# RT1064_CoreBoard.net
KiCad netlist of a schematic drawn in Altium Designer
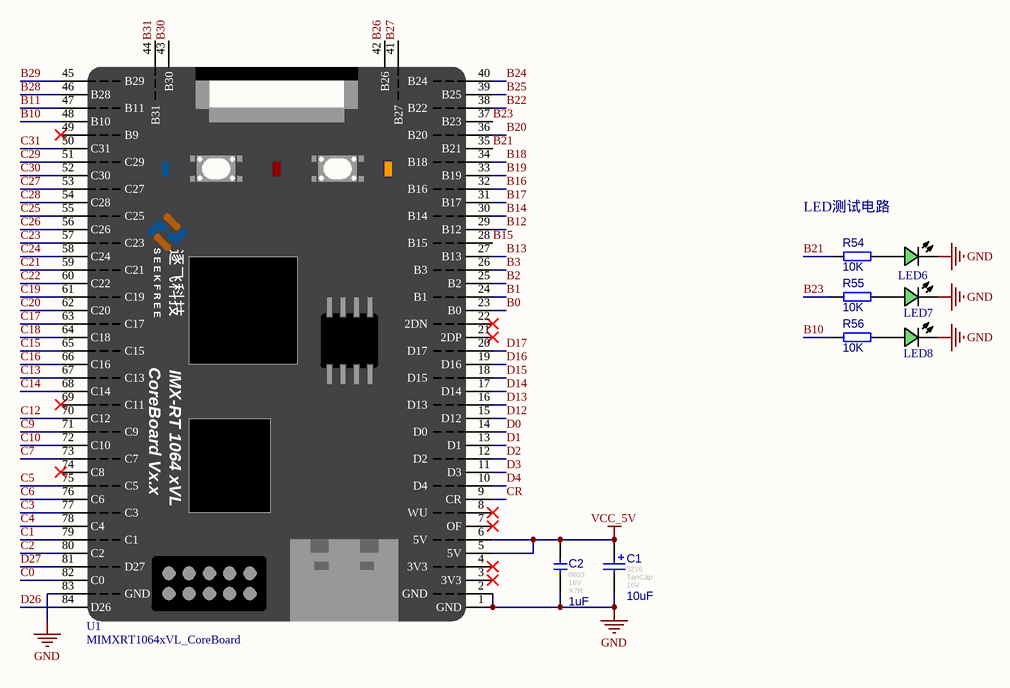
[diagram p0: RT1064_CoreBoard.SchDoc]

(export (version "E")
  (design (tool "Eeschema 10.0.6"))
  (components
    (comp (ref "C1")
      (value "10uF")
      (footprint "3216")
      (description "贴片钽电容 10uF 3216 16V")
      (fields
        (field (name "TYPE") "TanCap")
        (field (name "VOLTAGE") "16V")
        (field (name "Comment") "T-S 10uF 3216 16V")
      )
      (libsource (lib "RT1064_V1主板器件封装集成库") (part "T-S 10uF 3216 16V"))
    )
    (comp (ref "C2")
      (value "1uF")
      (footprint "0603")
      (description "贴片瓷片电容; MLCC; 0603(1608);")
      (fields
        (field (name "VOLTAGE") "16V")
        (field (name "TYPE") "X7R")
        (field (name "Comment") "1uF 16V X7R")
      )
      (libsource (lib "RT1064_V1主板器件封装集成库") (part "1uF 0603 16V X7R"))
    )
    (comp (ref "LED6")
      (value "翠绿贴片LED")
      (footprint "LEDC1608(0603)-L")
      (fields (field (name "PUBLISHER") "Altium Limited"))
      (libsource (lib "RT1064_V1主板器件封装集成库") (part "LED Chip Green"))
    )
    (comp (ref "LED7")
      (value "翠绿贴片LED")
      (footprint "LEDC1608(0603)-L")
      (fields (field (name "PUBLISHER") "Altium Limited"))
      (libsource (lib "RT1064_V1主板器件封装集成库") (part "LED Chip Green"))
    )
    (comp (ref "LED8")
      (value "翠绿贴片LED")
      (footprint "LEDC1608(0603)-L")
      (fields (field (name "PUBLISHER") "Altium Limited"))
      (libsource (lib "RT1064_V1主板器件封装集成库") (part "LED Chip Green"))
    )
    (comp (ref "R54")
      (value "10K")
      (footprint "RESC1608[0603]S-L")
      (description "贴片电阻")
      (fields (field (name "POWER") "1/8W") (field (name "TOLERANCE") "±1%"))
      (libsource (lib "RT1064_V1主板器件封装集成库") (part "Res-Chip"))
    )
    (comp (ref "R55")
      (value "10K")
      (footprint "RESC1608[0603]S-L")
      (description "贴片电阻")
      (fields (field (name "POWER") "1/8W") (field (name "TOLERANCE") "±1%"))
      (libsource (lib "RT1064_V1主板器件封装集成库") (part "Res-Chip"))
    )
    (comp (ref "R56")
      (value "10K")
      (footprint "RESC1608[0603]S-L")
      (description "贴片电阻")
      (fields (field (name "POWER") "1/8W") (field (name "TOLERANCE") "±1%"))
      (libsource (lib "RT1064_V1主板器件封装集成库") (part "Res-Chip"))
    )
    (comp (ref "U1")
      (value "MIMXRT1064xVL_CoreBoard")
      (footprint "MIMXRT1064xVL_CoreBoard - 3D")
      (description "逐飞科技i.MX RT1064核心板整体原理，可直接使用")
      (libsource (lib "RT1064 V1.2核心板原理库") (part "MIMXRT1064xVL_CoreBoard"))
    )
  )
  (nets
    (net (code "1") (name "/B0") (class "Default")
      (node (ref "U1") (pin "23") (pinfunction "B0_23") (pintype "passive"))
    )
    (net (code "2") (name "/B1") (class "Default")
      (node (ref "U1") (pin "24") (pinfunction "B1_24") (pintype "passive"))
    )
    (net (code "3") (name "/B2") (class "Default")
      (node (ref "U1") (pin "25") (pinfunction "B2_25") (pintype "passive"))
    )
    (net (code "4") (name "/B3") (class "Default")
      (node (ref "U1") (pin "26") (pinfunction "B3_26") (pintype "passive"))
    )
    (net (code "5") (name "/B10") (class "Default")
      (node (ref "R56") (pin "2") (pinfunction "2_2") (pintype "passive"))
      (node (ref "U1") (pin "48") (pinfunction "B10_48") (pintype "passive"))
    )
    (net (code "6") (name "/B11") (class "Default")
      (node (ref "U1") (pin "47") (pinfunction "B11_47") (pintype "passive"))
    )
    (net (code "7") (name "/B12") (class "Default")
      (node (ref "U1") (pin "29") (pinfunction "B12_29") (pintype "passive"))
    )
    (net (code "8") (name "/B13") (class "Default")
      (node (ref "U1") (pin "27") (pinfunction "B13_27") (pintype "passive"))
    )
    (net (code "9") (name "/B14") (class "Default")
      (node (ref "U1") (pin "30") (pinfunction "B14_30") (pintype "passive"))
    )
    (net (code "10") (name "/B15") (class "Default")
      (node (ref "U1") (pin "28") (pinfunction "B15_28") (pintype "passive"))
    )
    (net (code "11") (name "/B16") (class "Default")
      (node (ref "U1") (pin "32") (pinfunction "B16_32") (pintype "passive"))
    )
    (net (code "12") (name "/B17") (class "Default")
      (node (ref "U1") (pin "31") (pinfunction "B17_31") (pintype "passive"))
    )
    (net (code "13") (name "/B18") (class "Default")
      (node (ref "U1") (pin "34") (pinfunction "B18_34") (pintype "passive"))
    )
    (net (code "14") (name "/B19") (class "Default")
      (node (ref "U1") (pin "33") (pinfunction "B19_33") (pintype "passive"))
    )
    (net (code "15") (name "/B20") (class "Default")
      (node (ref "U1") (pin "36") (pinfunction "B20_36") (pintype "passive"))
    )
    (net (code "16") (name "/B21") (class "Default")
      (node (ref "R54") (pin "2") (pinfunction "2_2") (pintype "passive"))
      (node (ref "U1") (pin "35") (pinfunction "B21_35") (pintype "passive"))
    )
    (net (code "17") (name "/B22") (class "Default")
      (node (ref "U1") (pin "38") (pinfunction "B22_38") (pintype "passive"))
    )
    (net (code "18") (name "/B23") (class "Default")
      (node (ref "R55") (pin "2") (pinfunction "2_2") (pintype "passive"))
      (node (ref "U1") (pin "37") (pinfunction "B23_37") (pintype "passive"))
    )
    (net (code "19") (name "/B24") (class "Default")
      (node (ref "U1") (pin "40") (pinfunction "B24_40") (pintype "passive"))
    )
    (net (code "20") (name "/B25") (class "Default")
      (node (ref "U1") (pin "39") (pinfunction "B25_39") (pintype "passive"))
    )
    (net (code "21") (name "/B26") (class "Default")
      (node (ref "U1") (pin "42") (pinfunction "B26_42") (pintype "passive"))
    )
    (net (code "22") (name "/B27") (class "Default")
      (node (ref "U1") (pin "41") (pinfunction "B27_41") (pintype "passive"))
    )
    (net (code "23") (name "/B28") (class "Default")
      (node (ref "U1") (pin "46") (pinfunction "B28_46") (pintype "passive"))
    )
    (net (code "24") (name "/B29") (class "Default")
      (node (ref "U1") (pin "45") (pinfunction "B29_45") (pintype "passive"))
    )
    (net (code "25") (name "/B30") (class "Default")
      (node (ref "U1") (pin "43") (pinfunction "B30_43") (pintype "passive"))
    )
    (net (code "26") (name "/B31") (class "Default")
      (node (ref "U1") (pin "44") (pinfunction "B31_44") (pintype "passive"))
    )
    (net (code "27") (name "/C0") (class "Default")
      (node (ref "U1") (pin "82") (pinfunction "C0_82") (pintype "passive"))
    )
    (net (code "28") (name "/C1") (class "Default")
      (node (ref "U1") (pin "79") (pinfunction "C1_79") (pintype "passive"))
    )
    (net (code "29") (name "/C2") (class "Default")
      (node (ref "U1") (pin "80") (pinfunction "C2_80") (pintype "passive"))
    )
    (net (code "30") (name "/C3") (class "Default")
      (node (ref "U1") (pin "77") (pinfunction "C3_77") (pintype "passive"))
    )
    (net (code "31") (name "/C4") (class "Default")
      (node (ref "U1") (pin "78") (pinfunction "C4_78") (pintype "passive"))
    )
    (net (code "32") (name "/C5") (class "Default")
      (node (ref "U1") (pin "75") (pinfunction "C5_75") (pintype "passive"))
    )
    (net (code "33") (name "/C6") (class "Default")
      (node (ref "U1") (pin "76") (pinfunction "C6_76") (pintype "passive"))
    )
    (net (code "34") (name "/C7") (class "Default")
      (node (ref "U1") (pin "73") (pinfunction "C7_73") (pintype "passive"))
    )
    (net (code "35") (name "/C9") (class "Default")
      (node (ref "U1") (pin "71") (pinfunction "C9_71") (pintype "passive"))
    )
    (net (code "36") (name "/C10") (class "Default")
      (node (ref "U1") (pin "72") (pinfunction "C10_72") (pintype "passive"))
    )
    (net (code "37") (name "/C12") (class "Default")
      (node (ref "U1") (pin "70") (pinfunction "C12_70") (pintype "passive"))
    )
    (net (code "38") (name "/C13") (class "Default")
      (node (ref "U1") (pin "67") (pinfunction "C13_67") (pintype "passive"))
    )
    (net (code "39") (name "/C14") (class "Default")
      (node (ref "U1") (pin "68") (pinfunction "C14_68") (pintype "passive"))
    )
    (net (code "40") (name "/C15") (class "Default")
      (node (ref "U1") (pin "65") (pinfunction "C15_65") (pintype "passive"))
    )
    (net (code "41") (name "/C16") (class "Default")
      (node (ref "U1") (pin "66") (pinfunction "C16_66") (pintype "passive"))
    )
    (net (code "42") (name "/C17") (class "Default")
      (node (ref "U1") (pin "63") (pinfunction "C17_63") (pintype "passive"))
    )
    (net (code "43") (name "/C18") (class "Default")
      (node (ref "U1") (pin "64") (pinfunction "C18_64") (pintype "passive"))
    )
    (net (code "44") (name "/C19") (class "Default")
      (node (ref "U1") (pin "61") (pinfunction "C19_61") (pintype "passive"))
    )
    (net (code "45") (name "/C20") (class "Default")
      (node (ref "U1") (pin "62") (pinfunction "C20_62") (pintype "passive"))
    )
    (net (code "46") (name "/C21") (class "Default")
      (node (ref "U1") (pin "59") (pinfunction "C21_59") (pintype "passive"))
    )
    (net (code "47") (name "/C22") (class "Default")
      (node (ref "U1") (pin "60") (pinfunction "C22_60") (pintype "passive"))
    )
    (net (code "48") (name "/C23") (class "Default")
      (node (ref "U1") (pin "57") (pinfunction "C23_57") (pintype "passive"))
    )
    (net (code "49") (name "/C24") (class "Default")
      (node (ref "U1") (pin "58") (pinfunction "C24_58") (pintype "passive"))
    )
    (net (code "50") (name "/C25") (class "Default")
      (node (ref "U1") (pin "55") (pinfunction "C25_55") (pintype "passive"))
    )
    (net (code "51") (name "/C26") (class "Default")
      (node (ref "U1") (pin "56") (pinfunction "C26_56") (pintype "passive"))
    )
    (net (code "52") (name "/C27") (class "Default")
      (node (ref "U1") (pin "53") (pinfunction "C27_53") (pintype "passive"))
    )
    (net (code "53") (name "/C28") (class "Default")
      (node (ref "U1") (pin "54") (pinfunction "C28_54") (pintype "passive"))
    )
    (net (code "54") (name "/C29") (class "Default")
      (node (ref "U1") (pin "51") (pinfunction "C29_51") (pintype "passive"))
    )
    (net (code "55") (name "/C30") (class "Default")
      (node (ref "U1") (pin "52") (pinfunction "C30_52") (pintype "passive"))
    )
    (net (code "56") (name "/C31") (class "Default")
      (node (ref "U1") (pin "50") (pinfunction "C31_50") (pintype "passive"))
    )
    (net (code "57") (name "/CR") (class "Default")
      (node (ref "U1") (pin "9") (pinfunction "CR_9") (pintype "passive"))
    )
    (net (code "58") (name "/D0") (class "Default")
      (node (ref "U1") (pin "14") (pinfunction "D0_14") (pintype "passive"))
    )
    (net (code "59") (name "/D1") (class "Default")
      (node (ref "U1") (pin "13") (pinfunction "D1_13") (pintype "passive"))
    )
    (net (code "60") (name "/D2") (class "Default")
      (node (ref "U1") (pin "12") (pinfunction "D2_12") (pintype "passive"))
    )
    (net (code "61") (name "/D3") (class "Default")
      (node (ref "U1") (pin "11") (pinfunction "D3_11") (pintype "passive"))
    )
    (net (code "62") (name "/D4") (class "Default")
      (node (ref "U1") (pin "10") (pinfunction "D4_10") (pintype "passive"))
    )
    (net (code "63") (name "/D12") (class "Default")
      (node (ref "U1") (pin "15") (pinfunction "D12_15") (pintype "passive"))
    )
    (net (code "64") (name "/D13") (class "Default")
      (node (ref "U1") (pin "16") (pinfunction "D13_16") (pintype "passive"))
    )
    (net (code "65") (name "/D14") (class "Default")
      (node (ref "U1") (pin "17") (pinfunction "D14_17") (pintype "passive"))
    )
    (net (code "66") (name "/D15") (class "Default")
      (node (ref "U1") (pin "18") (pinfunction "D15_18") (pintype "passive"))
    )
    (net (code "67") (name "/D16") (class "Default")
      (node (ref "U1") (pin "19") (pinfunction "D16_19") (pintype "passive"))
    )
    (net (code "68") (name "/D17") (class "Default")
      (node (ref "U1") (pin "20") (pinfunction "D17_20") (pintype "passive"))
    )
    (net (code "69") (name "/D26") (class "Default")
      (node (ref "U1") (pin "84") (pinfunction "D26_84") (pintype "passive"))
    )
    (net (code "70") (name "/D27") (class "Default")
      (node (ref "U1") (pin "81") (pinfunction "D27_81") (pintype "passive"))
    )
    (net (code "71") (name "GND") (class "Default")
      (node (ref "C1") (pin "2") (pinfunction "2_2") (pintype "passive"))
      (node (ref "C2") (pin "1") (pinfunction "1_1") (pintype "passive"))
      (node (ref "LED6") (pin "C") (pinfunction "C_C") (pintype "passive"))
      (node (ref "LED7") (pin "C") (pinfunction "C_C") (pintype "passive"))
      (node (ref "LED8") (pin "C") (pinfunction "C_C") (pintype "passive"))
      (node (ref "U1") (pin "1") (pinfunction "GND_1") (pintype "passive"))
      (node (ref "U1") (pin "2") (pinfunction "GND_2") (pintype "passive"))
      (node (ref "U1") (pin "83") (pinfunction "GND_83") (pintype "passive"))
    )
    (net (code "72") (name "Net-(LED6-PadA)") (class "Default")
      (node (ref "LED6") (pin "A") (pinfunction "A_A") (pintype "passive"))
      (node (ref "R54") (pin "1") (pinfunction "1_1") (pintype "passive"))
    )
    (net (code "73") (name "Net-(LED7-PadA)") (class "Default")
      (node (ref "LED7") (pin "A") (pinfunction "A_A") (pintype "passive"))
      (node (ref "R55") (pin "1") (pinfunction "1_1") (pintype "passive"))
    )
    (net (code "74") (name "Net-(LED8-PadA)") (class "Default")
      (node (ref "LED8") (pin "A") (pinfunction "A_A") (pintype "passive"))
      (node (ref "R56") (pin "1") (pinfunction "1_1") (pintype "passive"))
    )
    (net (code "75") (name "VCC_5V") (class "Default")
      (node (ref "C1") (pin "1") (pinfunction "1_1") (pintype "passive"))
      (node (ref "C2") (pin "2") (pinfunction "2_2") (pintype "passive"))
      (node (ref "U1") (pin "5") (pinfunction "5V_5") (pintype "passive"))
      (node (ref "U1") (pin "6") (pinfunction "5V_6") (pintype "passive"))
    )
    (net (code "76") (name "unconnected-(U1-2DN-Pad22)") (class "Default")
      (node (ref "U1") (pin "22") (pinfunction "2DN_22") (pintype "passive+no_connect"))
    )
    (net (code "77") (name "unconnected-(U1-2DP-Pad21)") (class "Default")
      (node (ref "U1") (pin "21") (pinfunction "2DP_21") (pintype "passive+no_connect"))
    )
    (net (code "78") (name "unconnected-(U1-3V3-Pad3)") (class "Default")
      (node (ref "U1") (pin "3") (pinfunction "3V3_3") (pintype "passive+no_connect"))
    )
    (net (code "79") (name "unconnected-(U1-3V3-Pad4)") (class "Default")
      (node (ref "U1") (pin "4") (pinfunction "3V3_4") (pintype "passive+no_connect"))
    )
    (net (code "80") (name "unconnected-(U1-B9-Pad49)") (class "Default")
      (node (ref "U1") (pin "49") (pinfunction "B9_49") (pintype "passive+no_connect"))
    )
    (net (code "81") (name "unconnected-(U1-C8-Pad74)") (class "Default")
      (node (ref "U1") (pin "74") (pinfunction "C8_74") (pintype "passive+no_connect"))
    )
    (net (code "82") (name "unconnected-(U1-C11-Pad69)") (class "Default")
      (node (ref "U1") (pin "69") (pinfunction "C11_69") (pintype "passive+no_connect"))
    )
    (net (code "83") (name "unconnected-(U1-OF-Pad7)") (class "Default")
      (node (ref "U1") (pin "7") (pinfunction "OF_7") (pintype "passive+no_connect"))
    )
    (net (code "84") (name "unconnected-(U1-WU-Pad8)") (class "Default")
      (node (ref "U1") (pin "8") (pinfunction "WU_8") (pintype "passive+no_connect"))
    )
  )
)
